# BMC1.net
KiCad netlist of a schematic drawn in EAGLE
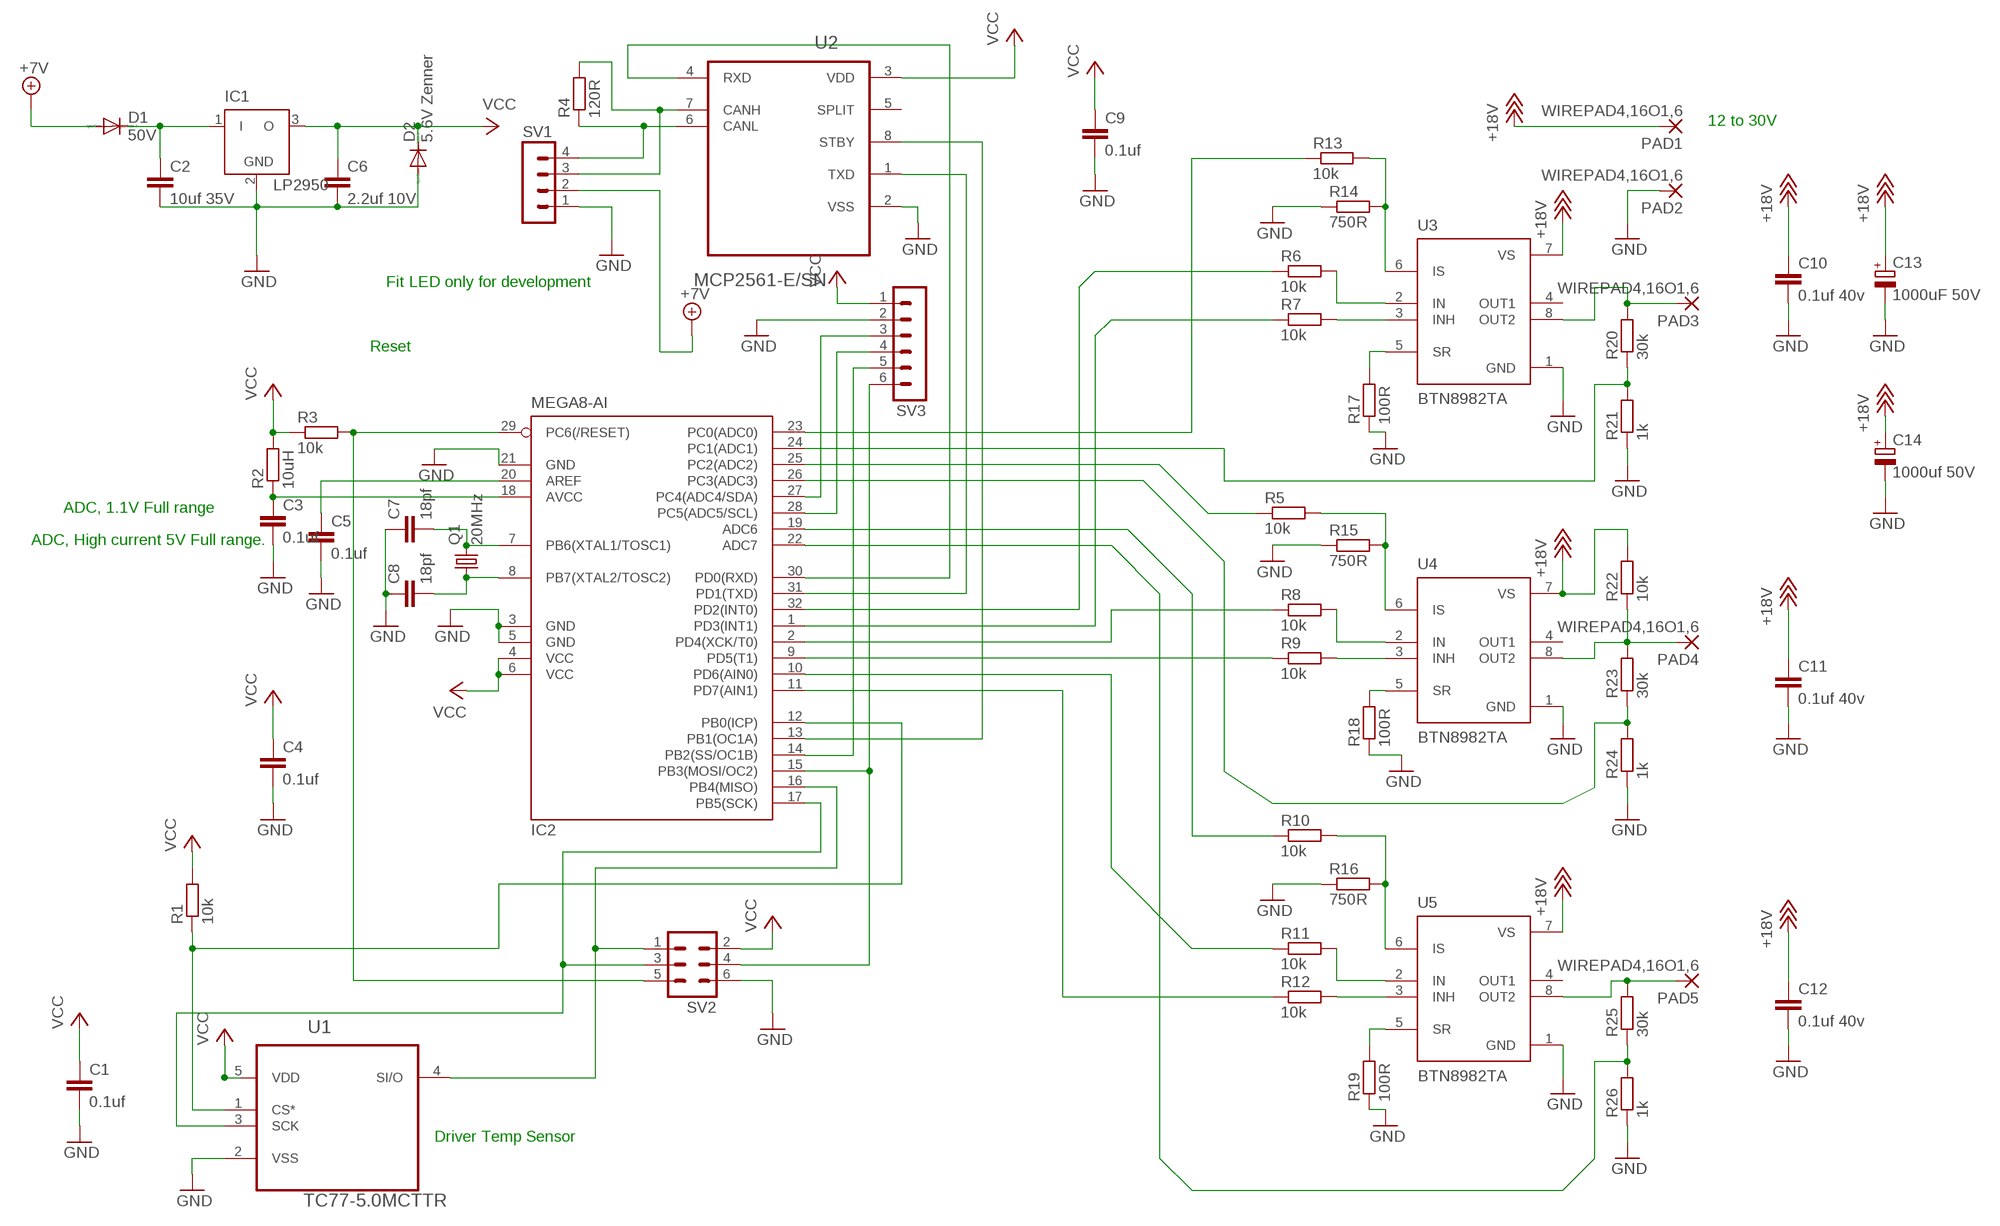
[diagram p0: schematic, sheet 1]

(export (version "E")
  (design (tool "Eeschema 10.0.6"))
  (components
    (comp (ref "C1")
      (value "0.1uf")
      (footprint "eagle-import:C0805")
      (fields (field (name "MF") "KEMET") (field (name "MPN") "C0805C104J5RACTU"))
      (libsource (lib "eagle-import") (part "C-EUC0805"))
    )
    (comp (ref "C2")
      (value "10uf 35V")
      (footprint "eagle-import:C0805")
      (fields (field (name "MF") "MURATA") (field (name "MPN") "GRM32ER7YA106KA12L"))
      (libsource (lib "eagle-import") (part "C-EUC0805"))
    )
    (comp (ref "C3")
      (value "0.1uf")
      (footprint "eagle-import:C0805")
      (fields (field (name "MF") "WALSIN") (field (name "MPN") "0805B104K500CT"))
      (libsource (lib "eagle-import") (part "C-EUC0805"))
    )
    (comp (ref "C4")
      (value "0.1uf")
      (footprint "eagle-import:C0805")
      (fields (field (name "MF") "KEMET") (field (name "MPN") "C0805C104J5RACTU"))
      (libsource (lib "eagle-import") (part "C-EUC0805"))
    )
    (comp (ref "C5")
      (value "0.1uf")
      (footprint "eagle-import:C0805")
      (fields (field (name "MF") "WALSIN") (field (name "MPN") "0805B104K500CT"))
      (libsource (lib "eagle-import") (part "C-EUC0805"))
    )
    (comp (ref "C6")
      (value "2.2uf 10V")
      (footprint "eagle-import:C0805")
      (fields (field (name "MF") "KEMET") (field (name "MPN") "C0805C225K8RACAUTO"))
      (libsource (lib "eagle-import") (part "C-EUC0805"))
    )
    (comp (ref "C7")
      (value "18pf")
      (footprint "eagle-import:C0805")
      (fields (field (name "MF") "WALSIN") (field (name "MPN") "0805N180J500CT"))
      (libsource (lib "eagle-import") (part "C-EUC0805"))
    )
    (comp (ref "C8")
      (value "18pf")
      (footprint "eagle-import:C0805")
      (fields (field (name "MF") "WALSIN") (field (name "MPN") "0805N180J500CT"))
      (libsource (lib "eagle-import") (part "C-EUC0805"))
    )
    (comp (ref "C9")
      (value "0.1uf")
      (footprint "eagle-import:C0805")
      (fields (field (name "MF") "KEMET") (field (name "MPN") "C0805C104J5RACTU"))
      (libsource (lib "eagle-import") (part "C-EUC0805"))
    )
    (comp (ref "C10")
      (value "0.1uf 40v")
      (footprint "eagle-import:C0805")
      (fields (field (name "MF") "KEMET") (field (name "MPN") "C0805C104J5RACTU"))
      (libsource (lib "eagle-import") (part "C-EUC0805"))
    )
    (comp (ref "C11")
      (value "0.1uf 40v")
      (footprint "eagle-import:C0805")
      (fields (field (name "MF") "KEMET") (field (name "MPN") "C0805C104J5RACTU"))
      (libsource (lib "eagle-import") (part "C-EUC0805"))
    )
    (comp (ref "C12")
      (value "0.1uf 40v")
      (footprint "eagle-import:C0805")
      (fields (field (name "MF") "KEMET") (field (name "MPN") "C0805C104J5RACTU"))
      (libsource (lib "eagle-import") (part "C-EUC0805"))
    )
    (comp (ref "C13")
      (value "1000uF 50V")
      (footprint "eagle-import:UD-10X10_NICHICON")
      (fields (field (name "MF") "KEMET") (field (name "MPN") "T491A105K016AT"))
      (libsource (lib "eagle-import") (part "CPOL-EUUD-10X10"))
    )
    (comp (ref "C14")
      (value "1000uf 50V")
      (footprint "eagle-import:E5-10,5")
      (libsource (lib "eagle-import") (part "resistor_CPOL-EUE5-10.5"))
    )
    (comp (ref "D1")
      (value "50V")
      (footprint "eagle-import:SMB")
      (fields (field (name "MF") "FAIRCHILD SEMICONDUCTOR") (field (name "MPN") "GF1A"))
      (libsource (lib "eagle-import") (part "DIODE-SMB"))
    )
    (comp (ref "D2")
      (value "5.6V Zenner")
      (footprint "eagle-import:DO214AA")
      (fields (field (name "MF") "ON SEMICONDUCTOR") (field (name "MPN") "1SMB5919BT3G"))
      (libsource (lib "eagle-import") (part "DIODE-DO214AA"))
    )
    (comp (ref "IC1")
      (value "LP2950")
      (footprint "eagle-import:DPACK")
      (fields (field (name "MF") "ON SEMICONDUCTOR") (field (name "MPN") "LP2950CDT-5.0G"))
      (libsource (lib "eagle-import") (part "LP2950"))
    )
    (comp (ref "IC2")
      (value "MEGA8-AI")
      (footprint "eagle-import:TQFP32-08")
      (fields (field (name "MPN") "ATMEGA8-16AU") (field (name "MF") "ATMEL"))
      (libsource (lib "eagle-import") (part "MEGA8-AI"))
    )
    (comp (ref "PAD1")
      (value "WIREPAD4,16O1,6")
      (footprint "eagle-import:4,16O1,6")
      (libsource (lib "eagle-import") (part "WIREPAD4,16O1,6"))
    )
    (comp (ref "PAD2")
      (value "WIREPAD4,16O1,6")
      (footprint "eagle-import:4,16O1,6")
      (libsource (lib "eagle-import") (part "WIREPAD4,16O1,6"))
    )
    (comp (ref "PAD3")
      (value "WIREPAD4,16O1,6")
      (footprint "eagle-import:4,16O1,6")
      (libsource (lib "eagle-import") (part "WIREPAD4,16O1,6"))
    )
    (comp (ref "PAD4")
      (value "WIREPAD4,16O1,6")
      (footprint "eagle-import:4,16O1,6")
      (libsource (lib "eagle-import") (part "WIREPAD4,16O1,6"))
    )
    (comp (ref "PAD5")
      (value "WIREPAD4,16O1,6")
      (footprint "eagle-import:4,16O1,6")
      (libsource (lib "eagle-import") (part "WIREPAD4,16O1,6"))
    )
    (comp (ref "Q1")
      (value "20MHz")
      (footprint "eagle-import:HC49_S")
      (fields (field (name "MF") "MULTICOMP") (field (name "MPN") "HC49SM-3.6864-30-50-60-16-ATF"))
      (libsource (lib "eagle-import") (part "CRYSTALHC49S"))
    )
    (comp (ref "R1")
      (value "10k")
      (footprint "eagle-import:R0805")
      (fields (field (name "MF") "WELWYN") (field (name "MPN") "WCR0805-10KFI"))
      (libsource (lib "eagle-import") (part "R-EU_R0805"))
    )
    (comp (ref "R2")
      (value "10uH")
      (footprint "eagle-import:R0805")
      (fields (field (name "MF") "TAIYO YUDEN") (field (name "MPN") "LB2012T100KR"))
      (libsource (lib "eagle-import") (part "R-EU_R0805"))
    )
    (comp (ref "R3")
      (value "10k")
      (footprint "eagle-import:R0805")
      (fields (field (name "MF") "WELWYN") (field (name "MPN") "WCR0805-10KFI"))
      (libsource (lib "eagle-import") (part "R-EU_R0805"))
    )
    (comp (ref "R4")
      (value "120R")
      (footprint "eagle-import:R0805")
      (fields (field (name "MF") "VISHAY") (field (name "MPN") "CRCW0805750RFKEA"))
      (libsource (lib "eagle-import") (part "R-EU_R0805"))
    )
    (comp (ref "R5")
      (value "10k")
      (footprint "eagle-import:R0805")
      (fields (field (name "MF") "WELWYN") (field (name "MPN") "WCR0805-10KFI"))
      (libsource (lib "eagle-import") (part "R-EU_R0805"))
    )
    (comp (ref "R6")
      (value "10k")
      (footprint "eagle-import:R0805")
      (fields (field (name "MF") "WELWYN") (field (name "MPN") "WCR0805-10KFI"))
      (libsource (lib "eagle-import") (part "R-EU_R0805"))
    )
    (comp (ref "R7")
      (value "10k")
      (footprint "eagle-import:R0805")
      (fields (field (name "MF") "WELWYN") (field (name "MPN") "WCR0805-10KFI"))
      (libsource (lib "eagle-import") (part "R-EU_R0805"))
    )
    (comp (ref "R8")
      (value "10k")
      (footprint "eagle-import:R0805")
      (fields (field (name "MF") "WELWYN") (field (name "MPN") "WCR0805-10KFI"))
      (libsource (lib "eagle-import") (part "R-EU_R0805"))
    )
    (comp (ref "R9")
      (value "10k")
      (footprint "eagle-import:R0805")
      (fields (field (name "MF") "WELWYN") (field (name "MPN") "WCR0805-10KFI"))
      (libsource (lib "eagle-import") (part "R-EU_R0805"))
    )
    (comp (ref "R10")
      (value "10k")
      (footprint "eagle-import:R0805")
      (fields (field (name "MF") "WELWYN") (field (name "MPN") "WCR0805-10KFI"))
      (libsource (lib "eagle-import") (part "R-EU_R0805"))
    )
    (comp (ref "R11")
      (value "10k")
      (footprint "eagle-import:R0805")
      (fields (field (name "MF") "WELWYN") (field (name "MPN") "WCR0805-10KFI"))
      (libsource (lib "eagle-import") (part "R-EU_R0805"))
    )
    (comp (ref "R12")
      (value "10k")
      (footprint "eagle-import:R0805")
      (fields (field (name "MF") "WELWYN") (field (name "MPN") "WCR0805-10KFI"))
      (libsource (lib "eagle-import") (part "R-EU_R0805"))
    )
    (comp (ref "R13")
      (value "10k")
      (footprint "eagle-import:R0805")
      (fields (field (name "MF") "WELWYN") (field (name "MPN") "WCR0805-10KFI"))
      (libsource (lib "eagle-import") (part "R-EU_R0805"))
    )
    (comp (ref "R14")
      (value "750R")
      (footprint "eagle-import:R0805")
      (fields (field (name "MF") "VISHAY") (field (name "MPN") "CRCW0805750RFKEA"))
      (libsource (lib "eagle-import") (part "R-EU_R0805"))
    )
    (comp (ref "R15")
      (value "750R")
      (footprint "eagle-import:R0805")
      (fields (field (name "MF") "VISHAY") (field (name "MPN") "CRCW0805750RFKEA"))
      (libsource (lib "eagle-import") (part "R-EU_R0805"))
    )
    (comp (ref "R16")
      (value "750R")
      (footprint "eagle-import:R0805")
      (fields (field (name "MF") "VISHAY") (field (name "MPN") "CRCW0805750RFKEA"))
      (libsource (lib "eagle-import") (part "R-EU_R0805"))
    )
    (comp (ref "R17")
      (value "100R")
      (footprint "eagle-import:R0805")
      (fields (field (name "MF") "WELWYN") (field (name "MPN") "WCR0805-100RFI"))
      (libsource (lib "eagle-import") (part "R-EU_R0805"))
    )
    (comp (ref "R18")
      (value "100R")
      (footprint "eagle-import:R0805")
      (fields (field (name "MF") "WELWYN") (field (name "MPN") "WCR0805-100RFI"))
      (libsource (lib "eagle-import") (part "R-EU_R0805"))
    )
    (comp (ref "R19")
      (value "100R")
      (footprint "eagle-import:R0805")
      (fields (field (name "MF") "WELWYN") (field (name "MPN") "WCR0805-100RFI"))
      (libsource (lib "eagle-import") (part "R-EU_R0805"))
    )
    (comp (ref "R20")
      (value "30k")
      (footprint "eagle-import:R0805")
      (fields (field (name "MF") "VISHAY") (field (name "MPN") "CRCW080530K0FKEA"))
      (libsource (lib "eagle-import") (part "R-EU_R0805"))
    )
    (comp (ref "R21")
      (value "1k")
      (footprint "eagle-import:R0805")
      (fields (field (name "MF") "VISHAY") (field (name "MPN") "CRCW08051K00FKEA"))
      (libsource (lib "eagle-import") (part "R-EU_R0805"))
    )
    (comp (ref "R22")
      (value "10k")
      (footprint "eagle-import:R0805")
      (fields (field (name "MF") "WELWYN") (field (name "MPN") "WCR0805-10KFI"))
      (libsource (lib "eagle-import") (part "R-EU_R0805"))
    )
    (comp (ref "R23")
      (value "30k")
      (footprint "eagle-import:R0805")
      (fields (field (name "MF") "VISHAY") (field (name "MPN") "CRCW080530K0FKEA"))
      (libsource (lib "eagle-import") (part "R-EU_R0805"))
    )
    (comp (ref "R24")
      (value "1k")
      (footprint "eagle-import:R0805")
      (fields (field (name "MF") "VISHAY") (field (name "MPN") "CRCW08051K00FKEA"))
      (libsource (lib "eagle-import") (part "R-EU_R0805"))
    )
    (comp (ref "R25")
      (value "30k")
      (footprint "eagle-import:R0805")
      (fields (field (name "MF") "VISHAY") (field (name "MPN") "CRCW080530K0FKEA"))
      (libsource (lib "eagle-import") (part "R-EU_R0805"))
    )
    (comp (ref "R26")
      (value "1k")
      (footprint "eagle-import:R0805")
      (fields (field (name "MF") "VISHAY") (field (name "MPN") "CRCW08051K00FKEA"))
      (libsource (lib "eagle-import") (part "R-EU_R0805"))
    )
    (comp (ref "SV1")
      (value "MA04-1")
      (footprint "eagle-import:MA04-1")
      (libsource (lib "eagle-import") (part "MA04-1"))
    )
    (comp (ref "SV2")
      (value "MA03-2")
      (footprint "eagle-import:MA03-2")
      (libsource (lib "eagle-import") (part "MA03-2"))
    )
    (comp (ref "SV3")
      (value "MA06-1")
      (footprint "eagle-import:MA06-1")
      (libsource (lib "eagle-import") (part "MA06-1"))
    )
    (comp (ref "U1")
      (value "TC77-5.0MCTTR")
      (footprint "eagle-import:SOT95P290X145-5N")
      (fields (field (name "MF") "MICROCHIP"))
      (libsource (lib "eagle-import") (part "TC77-5.0MCTTR"))
    )
    (comp (ref "U2")
      (value "MCP2561-E/SN")
      (footprint "eagle-import:SOIC127P600X175-8N")
      (libsource (lib "eagle-import") (part "MCP2561-E/SN"))
    )
    (comp (ref "U3")
      (value "BTN8982TA")
      (footprint "eagle-import:TO127P1500X440-8N-1")
      (fields (field (name "MF") "INFINEON"))
      (libsource (lib "eagle-import") (part "BTN8982TA"))
    )
    (comp (ref "U4")
      (value "BTN8982TA")
      (footprint "eagle-import:TO127P1500X440-8N-1")
      (fields (field (name "MF") "INFINEON"))
      (libsource (lib "eagle-import") (part "BTN8982TA"))
    )
    (comp (ref "U5")
      (value "BTN8982TA")
      (footprint "eagle-import:TO127P1500X440-8N-1")
      (fields (field (name "MF") "INFINEON"))
      (libsource (lib "eagle-import") (part "BTN8982TA"))
    )
  )
  (nets
    (net (code "1") (name "+7V") (class "Default")
      (node (ref "D1") (pin "A") (pinfunction "A_A") (pintype "passive"))
      (node (ref "SV1") (pin "2") (pinfunction "2_2") (pintype "passive"))
    )
    (net (code "2") (name "+18V") (class "Default")
      (node (ref "C10") (pin "1") (pinfunction "1_1") (pintype "passive"))
      (node (ref "C11") (pin "1") (pinfunction "1_1") (pintype "passive"))
      (node (ref "C12") (pin "1") (pinfunction "1_1") (pintype "passive"))
      (node (ref "C13") (pin "+") (pinfunction "+_+") (pintype "passive"))
      (node (ref "C14") (pin "+") (pinfunction "+_+") (pintype "passive"))
      (node (ref "PAD1") (pin "1") (pinfunction "P_1") (pintype "passive"))
      (node (ref "R22") (pin "2") (pinfunction "2_2") (pintype "passive"))
      (node (ref "U3") (pin "7") (pinfunction "VS_7") (pintype "power_in"))
      (node (ref "U4") (pin "7") (pinfunction "VS_7") (pintype "power_in"))
      (node (ref "U5") (pin "7") (pinfunction "VS_7") (pintype "power_in"))
    )
    (net (code "3") (name "GND") (class "Default")
      (node (ref "C1") (pin "2") (pinfunction "2_2") (pintype "passive"))
      (node (ref "C10") (pin "2") (pinfunction "2_2") (pintype "passive"))
      (node (ref "C11") (pin "2") (pinfunction "2_2") (pintype "passive"))
      (node (ref "C12") (pin "2") (pinfunction "2_2") (pintype "passive"))
      (node (ref "C13") (pin "-") (pinfunction "-_-") (pintype "passive"))
      (node (ref "C14") (pin "-") (pinfunction "-_-") (pintype "passive"))
      (node (ref "C2") (pin "2") (pinfunction "2_2") (pintype "passive"))
      (node (ref "C3") (pin "2") (pinfunction "2_2") (pintype "passive"))
      (node (ref "C4") (pin "2") (pinfunction "2_2") (pintype "passive"))
      (node (ref "C5") (pin "2") (pinfunction "2_2") (pintype "passive"))
      (node (ref "C6") (pin "2") (pinfunction "2_2") (pintype "passive"))
      (node (ref "C7") (pin "1") (pinfunction "1_1") (pintype "passive"))
      (node (ref "C8") (pin "1") (pinfunction "1_1") (pintype "passive"))
      (node (ref "C9") (pin "2") (pinfunction "2_2") (pintype "passive"))
      (node (ref "D2") (pin "A") (pinfunction "A_A") (pintype "passive"))
      (node (ref "IC1") (pin "2") (pinfunction "GND_2") (pintype "power_in"))
      (node (ref "IC2") (pin "21") (pinfunction "GND_21") (pintype "power_in"))
      (node (ref "IC2") (pin "3") (pinfunction "GND_3") (pintype "power_in"))
      (node (ref "IC2") (pin "5") (pinfunction "GND_5") (pintype "power_in"))
      (node (ref "PAD2") (pin "1") (pinfunction "P_1") (pintype "passive"))
      (node (ref "R14") (pin "1") (pinfunction "1_1") (pintype "passive"))
      (node (ref "R15") (pin "1") (pinfunction "1_1") (pintype "passive"))
      (node (ref "R16") (pin "1") (pinfunction "1_1") (pintype "passive"))
      (node (ref "R17") (pin "1") (pinfunction "1_1") (pintype "passive"))
      (node (ref "R18") (pin "1") (pinfunction "1_1") (pintype "passive"))
      (node (ref "R19") (pin "1") (pinfunction "1_1") (pintype "passive"))
      (node (ref "R21") (pin "1") (pinfunction "1_1") (pintype "passive"))
      (node (ref "R24") (pin "1") (pinfunction "1_1") (pintype "passive"))
      (node (ref "R26") (pin "1") (pinfunction "1_1") (pintype "passive"))
      (node (ref "SV1") (pin "1") (pinfunction "1_1") (pintype "passive"))
      (node (ref "SV2") (pin "6") (pinfunction "6_6") (pintype "passive"))
      (node (ref "SV3") (pin "2") (pinfunction "2_2") (pintype "passive"))
      (node (ref "U1") (pin "2") (pinfunction "VSS_2") (pintype "power_in"))
      (node (ref "U2") (pin "2") (pinfunction "VSS_2") (pintype "power_in"))
      (node (ref "U3") (pin "1") (pinfunction "GND_1") (pintype "power_in"))
      (node (ref "U4") (pin "1") (pinfunction "GND_1") (pintype "power_in"))
      (node (ref "U5") (pin "1") (pinfunction "GND_1") (pintype "power_in"))
    )
    (net (code "4") (name "Net-(IC1-I)") (class "Default")
      (node (ref "C2") (pin "1") (pinfunction "1_1") (pintype "passive"))
      (node (ref "D1") (pin "C") (pinfunction "C_C") (pintype "passive"))
      (node (ref "IC1") (pin "1") (pinfunction "I_1") (pintype "input"))
    )
    (net (code "5") (name "Net-(IC2-ADC6)") (class "Default")
      (node (ref "IC2") (pin "19") (pinfunction "ADC6_19") (pintype "bidirectional"))
      (node (ref "R10") (pin "1") (pinfunction "1_1") (pintype "passive"))
    )
    (net (code "6") (name "Net-(IC2-ADC7)") (class "Default")
      (node (ref "IC2") (pin "22") (pinfunction "ADC7_22") (pintype "bidirectional"))
      (node (ref "R25") (pin "1") (pinfunction "1_1") (pintype "passive"))
      (node (ref "R26") (pin "2") (pinfunction "2_2") (pintype "passive"))
    )
    (net (code "7") (name "Net-(IC2-AREF)") (class "Default")
      (node (ref "C5") (pin "1") (pinfunction "1_1") (pintype "passive"))
      (node (ref "IC2") (pin "20") (pinfunction "AREF_20") (pintype "passive"))
    )
    (net (code "8") (name "Net-(IC2-AVCC)") (class "Default")
      (node (ref "C3") (pin "1") (pinfunction "1_1") (pintype "passive"))
      (node (ref "IC2") (pin "18") (pinfunction "AVCC_18") (pintype "power_in"))
      (node (ref "R2") (pin "1") (pinfunction "1_1") (pintype "passive"))
    )
    (net (code "9") (name "Net-(IC2-PB0(ICP))") (class "Default")
      (node (ref "IC2") (pin "12") (pinfunction "PB0(ICP)_12") (pintype "bidirectional"))
      (node (ref "R1") (pin "1") (pinfunction "1_1") (pintype "passive"))
      (node (ref "U1") (pin "1") (pinfunction "CS*_1") (pintype "input"))
    )
    (net (code "10") (name "Net-(IC2-PB1(OC1A))") (class "Default")
      (node (ref "IC2") (pin "13") (pinfunction "PB1(OC1A)_13") (pintype "bidirectional"))
      (node (ref "U2") (pin "8") (pinfunction "STBY_8") (pintype "input"))
    )
    (net (code "11") (name "Net-(IC2-PB2(SS{slash}OC1B))") (class "Default")
      (node (ref "IC2") (pin "14") (pinfunction "PB2(SS/OC1B)_14") (pintype "bidirectional"))
      (node (ref "SV3") (pin "5") (pinfunction "5_5") (pintype "passive"))
    )
    (net (code "12") (name "Net-(IC2-PB3(MOSI{slash}OC2))") (class "Default")
      (node (ref "IC2") (pin "15") (pinfunction "PB3(MOSI/OC2)_15") (pintype "bidirectional"))
      (node (ref "SV2") (pin "4") (pinfunction "4_4") (pintype "passive"))
      (node (ref "SV3") (pin "6") (pinfunction "6_6") (pintype "passive"))
    )
    (net (code "13") (name "Net-(IC2-PB4(MISO))") (class "Default")
      (node (ref "IC2") (pin "16") (pinfunction "PB4(MISO)_16") (pintype "bidirectional"))
      (node (ref "SV2") (pin "1") (pinfunction "1_1") (pintype "passive"))
      (node (ref "U1") (pin "4") (pinfunction "SI/O_4") (pintype "bidirectional"))
    )
    (net (code "14") (name "Net-(IC2-PB5(SCK))") (class "Default")
      (node (ref "IC2") (pin "17") (pinfunction "PB5(SCK)_17") (pintype "bidirectional"))
      (node (ref "SV2") (pin "3") (pinfunction "3_3") (pintype "passive"))
      (node (ref "U1") (pin "3") (pinfunction "SCK_3") (pintype "input"))
    )
    (net (code "15") (name "Net-(IC2-PB6(XTAL1{slash}TOSC1))") (class "Default")
      (node (ref "C7") (pin "2") (pinfunction "2_2") (pintype "passive"))
      (node (ref "IC2") (pin "7") (pinfunction "PB6(XTAL1/TOSC1)_7") (pintype "bidirectional"))
      (node (ref "Q1") (pin "2") (pinfunction "2_2") (pintype "passive"))
    )
    (net (code "16") (name "Net-(IC2-PB7(XTAL2{slash}TOSC2))") (class "Default")
      (node (ref "C8") (pin "2") (pinfunction "2_2") (pintype "passive"))
      (node (ref "IC2") (pin "8") (pinfunction "PB7(XTAL2/TOSC2)_8") (pintype "bidirectional"))
      (node (ref "Q1") (pin "1") (pinfunction "1_1") (pintype "passive"))
    )
    (net (code "17") (name "Net-(IC2-PC0(ADC0))") (class "Default")
      (node (ref "IC2") (pin "23") (pinfunction "PC0(ADC0)_23") (pintype "bidirectional"))
      (node (ref "R13") (pin "1") (pinfunction "1_1") (pintype "passive"))
    )
    (net (code "18") (name "Net-(IC2-PC1(ADC1))") (class "Default")
      (node (ref "IC2") (pin "24") (pinfunction "PC1(ADC1)_24") (pintype "bidirectional"))
      (node (ref "R20") (pin "1") (pinfunction "1_1") (pintype "passive"))
      (node (ref "R21") (pin "2") (pinfunction "2_2") (pintype "passive"))
    )
    (net (code "19") (name "Net-(IC2-PC2(ADC2))") (class "Default")
      (node (ref "IC2") (pin "25") (pinfunction "PC2(ADC2)_25") (pintype "bidirectional"))
      (node (ref "R5") (pin "1") (pinfunction "1_1") (pintype "passive"))
    )
    (net (code "20") (name "Net-(IC2-PC3(ADC3))") (class "Default")
      (node (ref "IC2") (pin "26") (pinfunction "PC3(ADC3)_26") (pintype "bidirectional"))
      (node (ref "R23") (pin "1") (pinfunction "1_1") (pintype "passive"))
      (node (ref "R24") (pin "2") (pinfunction "2_2") (pintype "passive"))
    )
    (net (code "21") (name "Net-(IC2-PC4(ADC4{slash}SDA))") (class "Default")
      (node (ref "IC2") (pin "27") (pinfunction "PC4(ADC4/SDA)_27") (pintype "bidirectional"))
      (node (ref "SV3") (pin "3") (pinfunction "3_3") (pintype "passive"))
    )
    (net (code "22") (name "Net-(IC2-PC5(ADC5{slash}SCL))") (class "Default")
      (node (ref "IC2") (pin "28") (pinfunction "PC5(ADC5/SCL)_28") (pintype "bidirectional"))
      (node (ref "SV3") (pin "4") (pinfunction "4_4") (pintype "passive"))
    )
    (net (code "23") (name "Net-(IC2-PC6({slash}RESET))") (class "Default")
      (node (ref "IC2") (pin "29") (pinfunction "PC6(/RESET)_29") (pintype "bidirectional"))
      (node (ref "R3") (pin "2") (pinfunction "2_2") (pintype "passive"))
      (node (ref "SV2") (pin "5") (pinfunction "5_5") (pintype "passive"))
    )
    (net (code "24") (name "Net-(IC2-PD0(RXD))") (class "Default")
      (node (ref "IC2") (pin "30") (pinfunction "PD0(RXD)_30") (pintype "bidirectional"))
      (node (ref "U2") (pin "4") (pinfunction "RXD_4") (pintype "output"))
    )
    (net (code "25") (name "Net-(IC2-PD1(TXD))") (class "Default")
      (node (ref "IC2") (pin "31") (pinfunction "PD1(TXD)_31") (pintype "bidirectional"))
      (node (ref "U2") (pin "1") (pinfunction "TXD_1") (pintype "input"))
    )
    (net (code "26") (name "Net-(IC2-PD2(INT0))") (class "Default")
      (node (ref "IC2") (pin "32") (pinfunction "PD2(INT0)_32") (pintype "bidirectional"))
      (node (ref "R6") (pin "1") (pinfunction "1_1") (pintype "passive"))
    )
    (net (code "27") (name "Net-(IC2-PD3(INT1))") (class "Default")
      (node (ref "IC2") (pin "1") (pinfunction "PD3(INT1)_1") (pintype "bidirectional"))
      (node (ref "R7") (pin "1") (pinfunction "1_1") (pintype "passive"))
    )
    (net (code "28") (name "Net-(IC2-PD4(XCK{slash}T0))") (class "Default")
      (node (ref "IC2") (pin "2") (pinfunction "PD4(XCK/T0)_2") (pintype "bidirectional"))
      (node (ref "R8") (pin "1") (pinfunction "1_1") (pintype "passive"))
    )
    (net (code "29") (name "Net-(IC2-PD5(T1))") (class "Default")
      (node (ref "IC2") (pin "9") (pinfunction "PD5(T1)_9") (pintype "bidirectional"))
      (node (ref "R9") (pin "1") (pinfunction "1_1") (pintype "passive"))
    )
    (net (code "30") (name "Net-(IC2-PD6(AIN0))") (class "Default")
      (node (ref "IC2") (pin "10") (pinfunction "PD6(AIN0)_10") (pintype "bidirectional"))
      (node (ref "R11") (pin "1") (pinfunction "1_1") (pintype "passive"))
    )
    (net (code "31") (name "Net-(IC2-PD7(AIN1))") (class "Default")
      (node (ref "IC2") (pin "11") (pinfunction "PD7(AIN1)_11") (pintype "bidirectional"))
      (node (ref "R12") (pin "1") (pinfunction "1_1") (pintype "passive"))
    )
    (net (code "32") (name "Net-(PAD3-P)") (class "Default")
      (node (ref "PAD3") (pin "1") (pinfunction "P_1") (pintype "passive"))
      (node (ref "R20") (pin "2") (pinfunction "2_2") (pintype "passive"))
      (node (ref "U3") (pin "8") (pinfunction "OUT2_8") (pintype "output"))
    )
    (net (code "33") (name "Net-(PAD4-P)") (class "Default")
      (node (ref "PAD4") (pin "1") (pinfunction "P_1") (pintype "passive"))
      (node (ref "R22") (pin "1") (pinfunction "1_1") (pintype "passive"))
      (node (ref "R23") (pin "2") (pinfunction "2_2") (pintype "passive"))
      (node (ref "U4") (pin "8") (pinfunction "OUT2_8") (pintype "output"))
    )
    (net (code "34") (name "Net-(PAD5-P)") (class "Default")
      (node (ref "PAD5") (pin "1") (pinfunction "P_1") (pintype "passive"))
      (node (ref "R25") (pin "2") (pinfunction "2_2") (pintype "passive"))
      (node (ref "U5") (pin "8") (pinfunction "OUT2_8") (pintype "output"))
    )
    (net (code "35") (name "Net-(U2-CANH)") (class "Default")
      (node (ref "R4") (pin "2") (pinfunction "2_2") (pintype "passive"))
      (node (ref "SV1") (pin "3") (pinfunction "3_3") (pintype "passive"))
      (node (ref "U2") (pin "7") (pinfunction "CANH_7") (pintype "bidirectional"))
    )
    (net (code "36") (name "Net-(U2-CANL)") (class "Default")
      (node (ref "R4") (pin "1") (pinfunction "1_1") (pintype "passive"))
      (node (ref "SV1") (pin "4") (pinfunction "4_4") (pintype "passive"))
      (node (ref "U2") (pin "6") (pinfunction "CANL_6") (pintype "bidirectional"))
    )
    (net (code "37") (name "Net-(U3-IN)") (class "Default")
      (node (ref "R6") (pin "2") (pinfunction "2_2") (pintype "passive"))
      (node (ref "U3") (pin "2") (pinfunction "IN_2") (pintype "input"))
    )
    (net (code "38") (name "Net-(U3-INH)") (class "Default")
      (node (ref "R7") (pin "2") (pinfunction "2_2") (pintype "passive"))
      (node (ref "U3") (pin "3") (pinfunction "INH_3") (pintype "input"))
    )
    (net (code "39") (name "Net-(U3-IS)") (class "Default")
      (node (ref "R13") (pin "2") (pinfunction "2_2") (pintype "passive"))
      (node (ref "R14") (pin "2") (pinfunction "2_2") (pintype "passive"))
      (node (ref "U3") (pin "6") (pinfunction "IS_6") (pintype "output"))
    )
    (net (code "40") (name "Net-(U3-SR)") (class "Default")
      (node (ref "R17") (pin "2") (pinfunction "2_2") (pintype "passive"))
      (node (ref "U3") (pin "5") (pinfunction "SR_5") (pintype "input"))
    )
    (net (code "41") (name "Net-(U4-IN)") (class "Default")
      (node (ref "R8") (pin "2") (pinfunction "2_2") (pintype "passive"))
      (node (ref "U4") (pin "2") (pinfunction "IN_2") (pintype "input"))
    )
    (net (code "42") (name "Net-(U4-INH)") (class "Default")
      (node (ref "R9") (pin "2") (pinfunction "2_2") (pintype "passive"))
      (node (ref "U4") (pin "3") (pinfunction "INH_3") (pintype "input"))
    )
    (net (code "43") (name "Net-(U4-IS)") (class "Default")
      (node (ref "R15") (pin "2") (pinfunction "2_2") (pintype "passive"))
      (node (ref "R5") (pin "2") (pinfunction "2_2") (pintype "passive"))
      (node (ref "U4") (pin "6") (pinfunction "IS_6") (pintype "output"))
    )
    (net (code "44") (name "Net-(U4-SR)") (class "Default")
      (node (ref "R18") (pin "2") (pinfunction "2_2") (pintype "passive"))
      (node (ref "U4") (pin "5") (pinfunction "SR_5") (pintype "input"))
    )
    (net (code "45") (name "Net-(U5-IN)") (class "Default")
      (node (ref "R11") (pin "2") (pinfunction "2_2") (pintype "passive"))
      (node (ref "U5") (pin "2") (pinfunction "IN_2") (pintype "input"))
    )
    (net (code "46") (name "Net-(U5-INH)") (class "Default")
      (node (ref "R12") (pin "2") (pinfunction "2_2") (pintype "passive"))
      (node (ref "U5") (pin "3") (pinfunction "INH_3") (pintype "input"))
    )
    (net (code "47") (name "Net-(U5-IS)") (class "Default")
      (node (ref "R10") (pin "2") (pinfunction "2_2") (pintype "passive"))
      (node (ref "R16") (pin "2") (pinfunction "2_2") (pintype "passive"))
      (node (ref "U5") (pin "6") (pinfunction "IS_6") (pintype "output"))
    )
    (net (code "48") (name "Net-(U5-SR)") (class "Default")
      (node (ref "R19") (pin "2") (pinfunction "2_2") (pintype "passive"))
      (node (ref "U5") (pin "5") (pinfunction "SR_5") (pintype "input"))
    )
    (net (code "49") (name "VCC") (class "Default")
      (node (ref "C1") (pin "1") (pinfunction "1_1") (pintype "passive"))
      (node (ref "C4") (pin "1") (pinfunction "1_1") (pintype "passive"))
      (node (ref "C6") (pin "1") (pinfunction "1_1") (pintype "passive"))
      (node (ref "C9") (pin "1") (pinfunction "1_1") (pintype "passive"))
      (node (ref "D2") (pin "C") (pinfunction "C_C") (pintype "passive"))
      (node (ref "IC1") (pin "3") (pinfunction "O_3") (pintype "input"))
      (node (ref "IC2") (pin "4") (pinfunction "VCC_4") (pintype "power_in"))
      (node (ref "IC2") (pin "6") (pinfunction "VCC_6") (pintype "power_in"))
      (node (ref "R1") (pin "2") (pinfunction "2_2") (pintype "passive"))
      (node (ref "R2") (pin "2") (pinfunction "2_2") (pintype "passive"))
      (node (ref "R3") (pin "1") (pinfunction "1_1") (pintype "passive"))
      (node (ref "SV2") (pin "2") (pinfunction "2_2") (pintype "passive"))
      (node (ref "SV3") (pin "1") (pinfunction "1_1") (pintype "passive"))
      (node (ref "U1") (pin "5") (pinfunction "VDD_5") (pintype "power_in"))
      (node (ref "U2") (pin "3") (pinfunction "VDD_3") (pintype "power_in"))
    )
    (net (code "50") (name "unconnected-(U2-SPLIT-Pad5)") (class "Default")
      (node (ref "U2") (pin "5") (pinfunction "SPLIT_5") (pintype "passive"))
    )
    (net (code "51") (name "unconnected-(U3-OUT1-Pad4)") (class "Default")
      (node (ref "U3") (pin "4") (pinfunction "OUT1_4") (pintype "output"))
    )
    (net (code "52") (name "unconnected-(U4-OUT1-Pad4)") (class "Default")
      (node (ref "U4") (pin "4") (pinfunction "OUT1_4") (pintype "output"))
    )
    (net (code "53") (name "unconnected-(U5-OUT1-Pad4)") (class "Default")
      (node (ref "U5") (pin "4") (pinfunction "OUT1_4") (pintype "output"))
    )
  )
)
